# 7_SEGMENT_PCB.net
KiCad netlist of a schematic drawn in EasyEDA
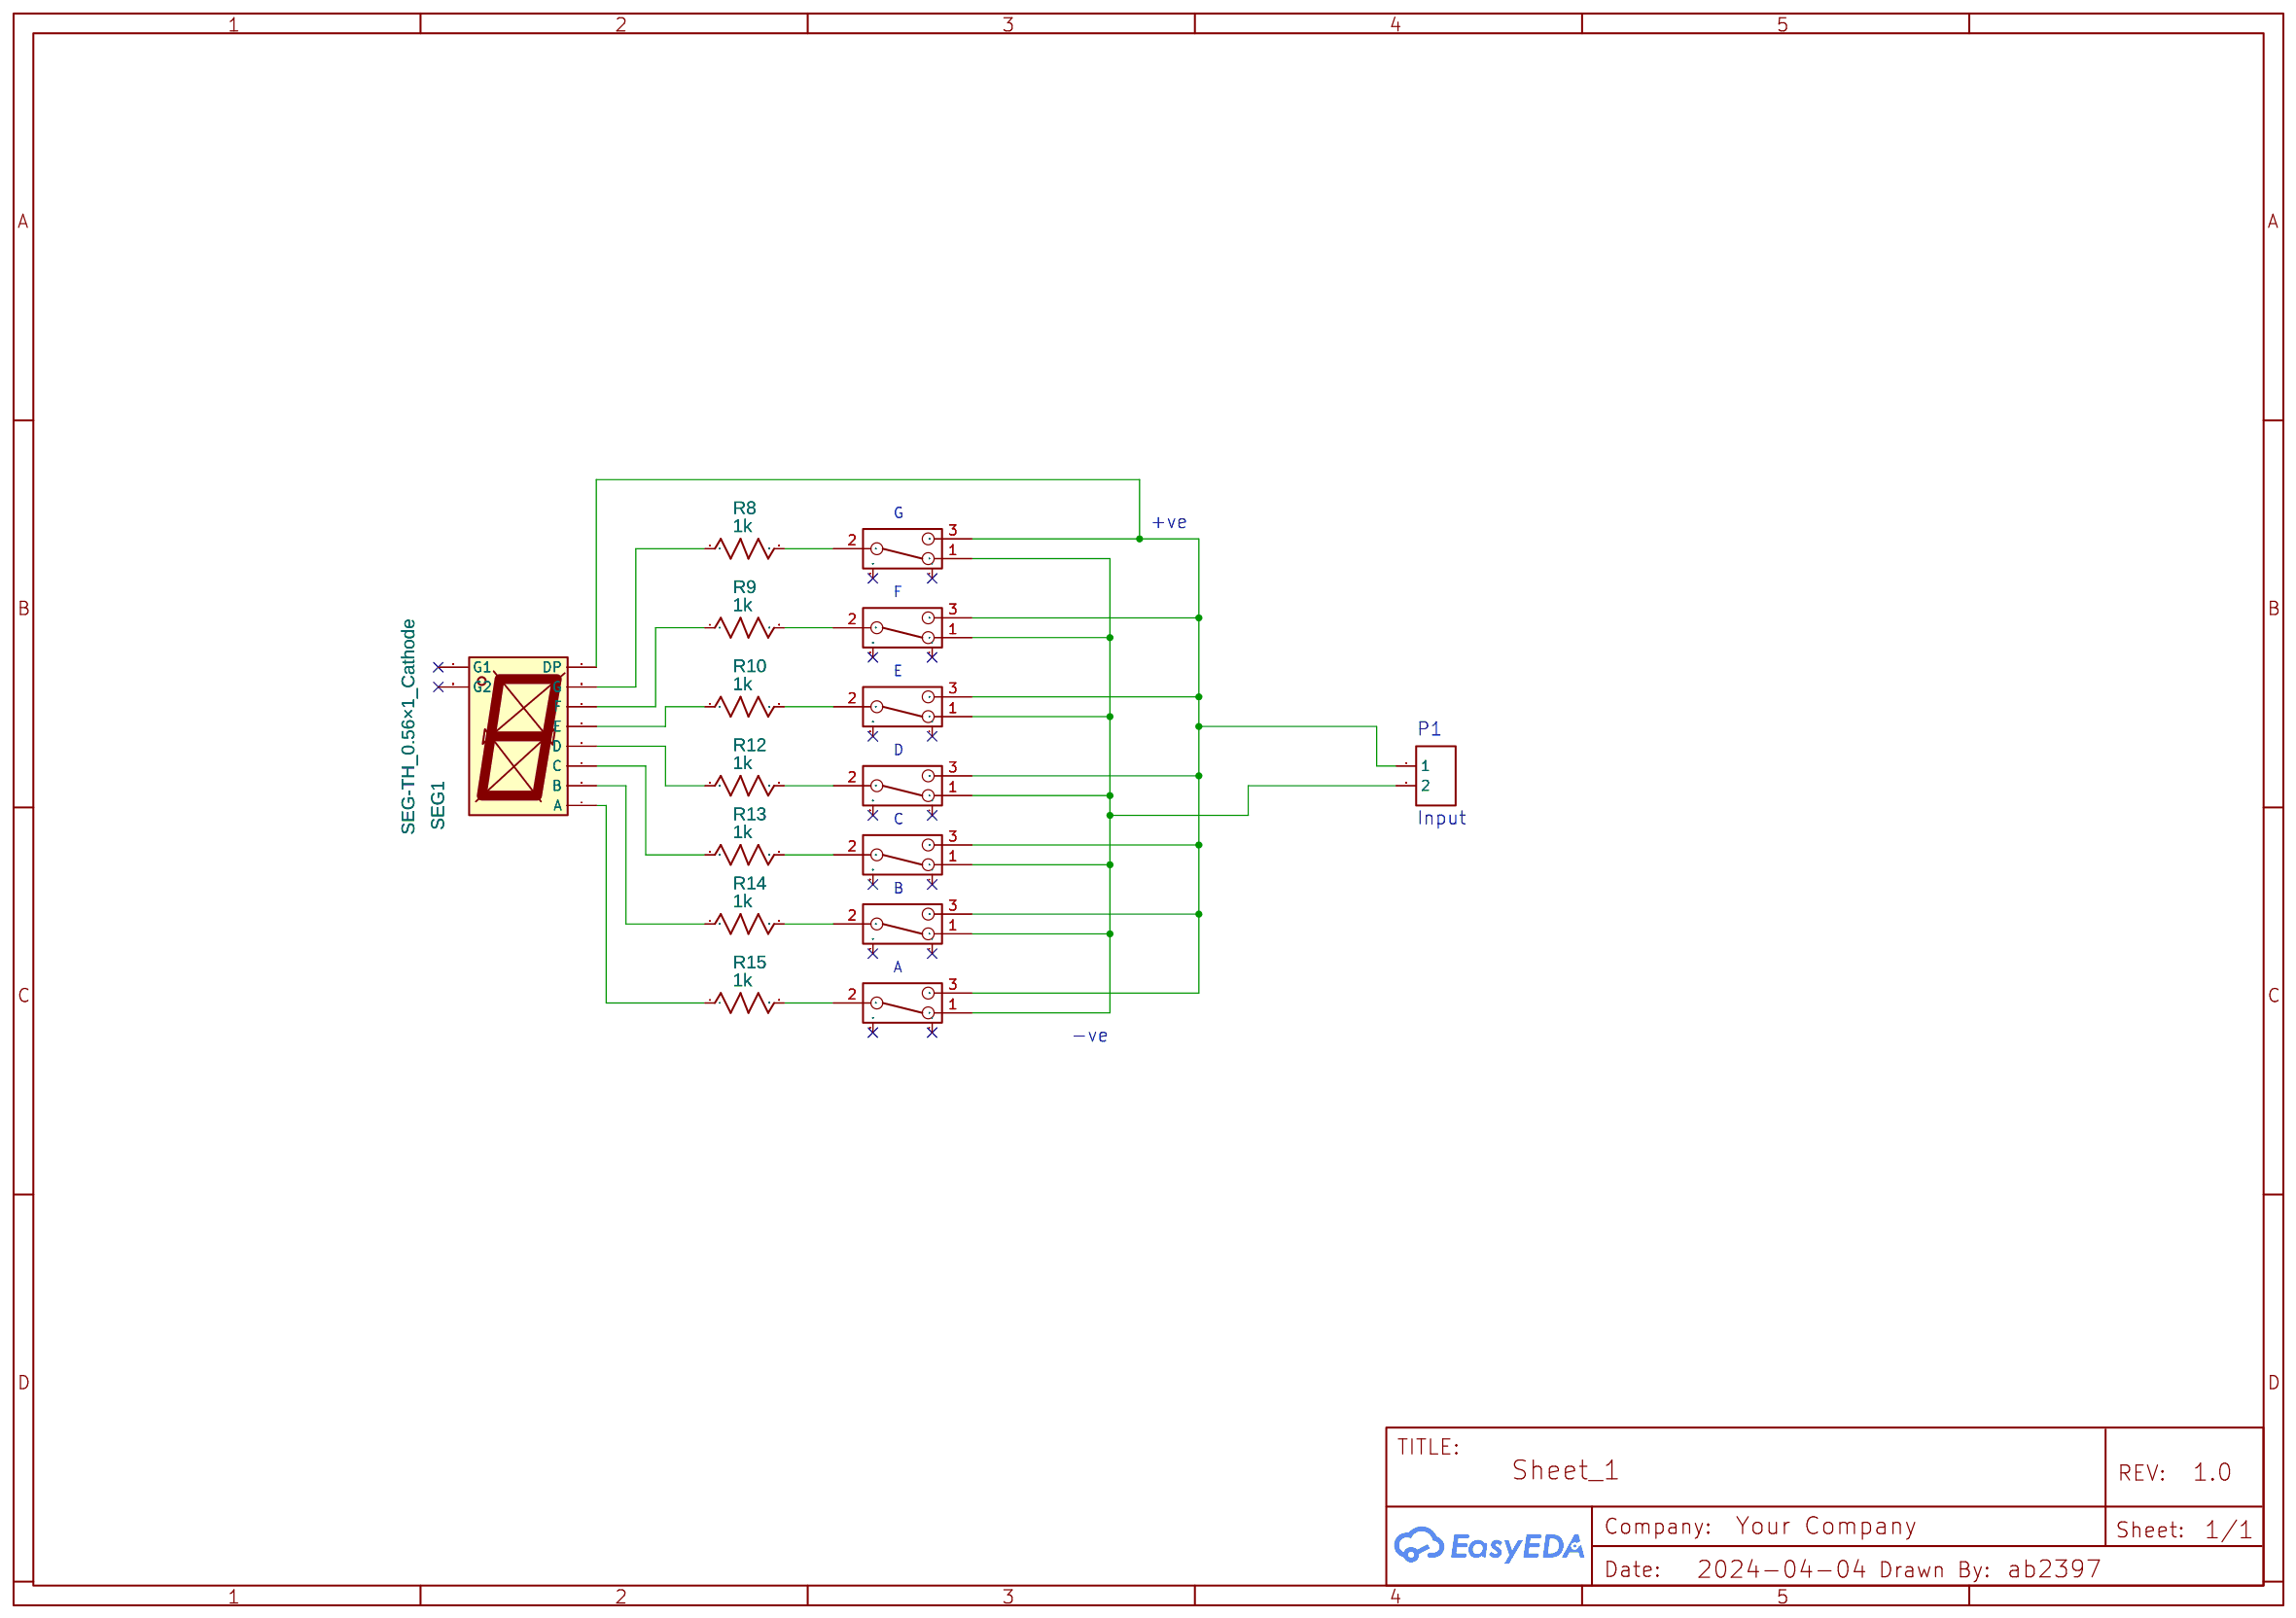
[diagram p0: schematic sheet]

(export (version "E")
  (design (tool "Eeschema 10.0.6"))
  (components
    (comp (ref "H1") (value "HDR-F-2.54_1x2") (libsource (lib "") (part "HDR-F-2.54_1x2")))
    (comp (ref "R8") (value "1k") (libsource (lib "") (part "R_0603_US")))
    (comp (ref "R9") (value "1k") (libsource (lib "") (part "R_0603_US")))
    (comp (ref "R10") (value "1k") (libsource (lib "") (part "R_0603_US")))
    (comp (ref "R12") (value "1k") (libsource (lib "") (part "R_0603_US")))
    (comp (ref "R13") (value "1k") (libsource (lib "") (part "R_0603_US")))
    (comp (ref "R14") (value "1k") (libsource (lib "") (part "R_0603_US")))
    (comp (ref "R15") (value "1k") (libsource (lib "") (part "R_0603_US")))
    (comp (ref "SEG1")
      (value "SEG-TH_0.56×1_Cathode")
      (fields (field (name "Manufacturer") "志浩"))
      (libsource (lib "") (part "SEG-TH_0.56×1_Cathode"))
    )
    (comp (ref "SW1")
      (value "SK-12D02-VG5")
      (fields (field (name "Manufacturer") "Rectangular Connectors - Contacts"))
      (libsource (lib "") (part "SK-12D02-VG5"))
    )
    (comp (ref "SW2")
      (value "SK-12D02-VG5")
      (fields (field (name "Manufacturer") "Rectangular Connectors - Contacts"))
      (libsource (lib "") (part "SK-12D02-VG5"))
    )
    (comp (ref "SW3")
      (value "SK-12D02-VG5")
      (fields (field (name "Manufacturer") "Rectangular Connectors - Contacts"))
      (libsource (lib "") (part "SK-12D02-VG5"))
    )
    (comp (ref "SW4")
      (value "SK-12D02-VG5")
      (fields (field (name "Manufacturer") "Rectangular Connectors - Contacts"))
      (libsource (lib "") (part "SK-12D02-VG5"))
    )
    (comp (ref "SW5")
      (value "SK-12D02-VG5")
      (fields (field (name "Manufacturer") "Rectangular Connectors - Contacts"))
      (libsource (lib "") (part "SK-12D02-VG5"))
    )
    (comp (ref "SW6")
      (value "SK-12D02-VG5")
      (fields (field (name "Manufacturer") "Rectangular Connectors - Contacts"))
      (libsource (lib "") (part "SK-12D02-VG5"))
    )
    (comp (ref "SW7")
      (value "SK-12D02-VG5")
      (fields (field (name "Manufacturer") "Rectangular Connectors - Contacts"))
      (libsource (lib "") (part "SK-12D02-VG5"))
    )
  )
  (nets
    (net (code "1") (name "Net-(H1-Pad2)") (class "Default")
      (node (ref "H1") (pin "2") (pinfunction "2_2") (pintype "input"))
      (node (ref "SW1") (pin "1") (pinfunction "1_1") (pintype "unspecified"))
      (node (ref "SW2") (pin "1") (pinfunction "1_1") (pintype "unspecified"))
      (node (ref "SW3") (pin "1") (pinfunction "1_1") (pintype "unspecified"))
      (node (ref "SW4") (pin "1") (pinfunction "1_1") (pintype "unspecified"))
      (node (ref "SW5") (pin "1") (pinfunction "1_1") (pintype "unspecified"))
      (node (ref "SW6") (pin "1") (pinfunction "1_1") (pintype "unspecified"))
      (node (ref "SW7") (pin "1") (pinfunction "1_1") (pintype "unspecified"))
    )
    (net (code "2") (name "Net-(R8-Pad2)") (class "Default")
      (node (ref "R8") (pin "2") (pinfunction "2_2") (pintype "unspecified"))
      (node (ref "SW1") (pin "2") (pinfunction "2_2") (pintype "unspecified"))
    )
    (net (code "3") (name "Net-(R9-Pad2)") (class "Default")
      (node (ref "R9") (pin "2") (pinfunction "2_2") (pintype "unspecified"))
      (node (ref "SW2") (pin "2") (pinfunction "2_2") (pintype "unspecified"))
    )
    (net (code "4") (name "Net-(R10-Pad2)") (class "Default")
      (node (ref "R10") (pin "2") (pinfunction "2_2") (pintype "unspecified"))
      (node (ref "SW3") (pin "2") (pinfunction "2_2") (pintype "unspecified"))
    )
    (net (code "5") (name "Net-(R12-Pad2)") (class "Default")
      (node (ref "R12") (pin "2") (pinfunction "2_2") (pintype "unspecified"))
      (node (ref "SW4") (pin "2") (pinfunction "2_2") (pintype "unspecified"))
    )
    (net (code "6") (name "Net-(R13-Pad2)") (class "Default")
      (node (ref "R13") (pin "2") (pinfunction "2_2") (pintype "unspecified"))
      (node (ref "SW5") (pin "2") (pinfunction "2_2") (pintype "unspecified"))
    )
    (net (code "7") (name "Net-(R14-Pad2)") (class "Default")
      (node (ref "R14") (pin "2") (pinfunction "2_2") (pintype "unspecified"))
      (node (ref "SW6") (pin "2") (pinfunction "2_2") (pintype "unspecified"))
    )
    (net (code "8") (name "Net-(R15-Pad2)") (class "Default")
      (node (ref "R15") (pin "2") (pinfunction "2_2") (pintype "unspecified"))
      (node (ref "SW7") (pin "2") (pinfunction "2_2") (pintype "unspecified"))
    )
    (net (code "9") (name "Net-(SEG1-A)") (class "Default")
      (node (ref "R15") (pin "1") (pinfunction "1_1") (pintype "unspecified"))
      (node (ref "SEG1") (pin "7") (pinfunction "A_7") (pintype "unspecified"))
    )
    (net (code "10") (name "Net-(SEG1-B)") (class "Default")
      (node (ref "R14") (pin "1") (pinfunction "1_1") (pintype "unspecified"))
      (node (ref "SEG1") (pin "6") (pinfunction "B_6") (pintype "unspecified"))
    )
    (net (code "11") (name "Net-(SEG1-C)") (class "Default")
      (node (ref "R13") (pin "1") (pinfunction "1_1") (pintype "unspecified"))
      (node (ref "SEG1") (pin "4") (pinfunction "C_4") (pintype "unspecified"))
    )
    (net (code "12") (name "Net-(SEG1-D)") (class "Default")
      (node (ref "R12") (pin "1") (pinfunction "1_1") (pintype "unspecified"))
      (node (ref "SEG1") (pin "2") (pinfunction "D_2") (pintype "unspecified"))
    )
    (net (code "13") (name "Net-(SEG1-DP)") (class "Default")
      (node (ref "H1") (pin "1") (pinfunction "1_1") (pintype "input"))
      (node (ref "SEG1") (pin "5") (pinfunction "DP_5") (pintype "unspecified"))
      (node (ref "SW1") (pin "3") (pinfunction "3_3") (pintype "unspecified"))
      (node (ref "SW2") (pin "3") (pinfunction "3_3") (pintype "unspecified"))
      (node (ref "SW3") (pin "3") (pinfunction "3_3") (pintype "unspecified"))
      (node (ref "SW4") (pin "3") (pinfunction "3_3") (pintype "unspecified"))
      (node (ref "SW5") (pin "3") (pinfunction "3_3") (pintype "unspecified"))
      (node (ref "SW6") (pin "3") (pinfunction "3_3") (pintype "unspecified"))
      (node (ref "SW7") (pin "3") (pinfunction "3_3") (pintype "unspecified"))
    )
    (net (code "14") (name "Net-(SEG1-E)") (class "Default")
      (node (ref "R10") (pin "1") (pinfunction "1_1") (pintype "unspecified"))
      (node (ref "SEG1") (pin "1") (pinfunction "E_1") (pintype "unspecified"))
    )
    (net (code "15") (name "Net-(SEG1-F)") (class "Default")
      (node (ref "R9") (pin "1") (pinfunction "1_1") (pintype "unspecified"))
      (node (ref "SEG1") (pin "9") (pinfunction "F_9") (pintype "unspecified"))
    )
    (net (code "16") (name "Net-(SEG1-G)") (class "Default")
      (node (ref "R8") (pin "1") (pinfunction "1_1") (pintype "unspecified"))
      (node (ref "SEG1") (pin "10") (pinfunction "G_10") (pintype "unspecified"))
    )
    (net (code "17") (name "unconnected-(SEG1-G1-Pad3)") (class "Default")
      (node (ref "SEG1") (pin "3") (pinfunction "G1_3") (pintype "unspecified+no_connect"))
    )
    (net (code "18") (name "unconnected-(SEG1-G2-Pad8)") (class "Default")
      (node (ref "SEG1") (pin "8") (pinfunction "G2_8") (pintype "unspecified+no_connect"))
    )
    (net (code "19") (name "unconnected-(SW1-Pad4)") (class "Default")
      (node (ref "SW1") (pin "4") (pinfunction "4_4") (pintype "unspecified+no_connect"))
    )
    (net (code "20") (name "unconnected-(SW1-Pad5)") (class "Default")
      (node (ref "SW1") (pin "5") (pinfunction "5_5") (pintype "unspecified+no_connect"))
    )
    (net (code "21") (name "unconnected-(SW2-Pad4)") (class "Default")
      (node (ref "SW2") (pin "4") (pinfunction "4_4") (pintype "unspecified+no_connect"))
    )
    (net (code "22") (name "unconnected-(SW2-Pad5)") (class "Default")
      (node (ref "SW2") (pin "5") (pinfunction "5_5") (pintype "unspecified+no_connect"))
    )
    (net (code "23") (name "unconnected-(SW3-Pad4)") (class "Default")
      (node (ref "SW3") (pin "4") (pinfunction "4_4") (pintype "unspecified+no_connect"))
    )
    (net (code "24") (name "unconnected-(SW3-Pad5)") (class "Default")
      (node (ref "SW3") (pin "5") (pinfunction "5_5") (pintype "unspecified+no_connect"))
    )
    (net (code "25") (name "unconnected-(SW4-Pad4)") (class "Default")
      (node (ref "SW4") (pin "4") (pinfunction "4_4") (pintype "unspecified+no_connect"))
    )
    (net (code "26") (name "unconnected-(SW4-Pad5)") (class "Default")
      (node (ref "SW4") (pin "5") (pinfunction "5_5") (pintype "unspecified+no_connect"))
    )
    (net (code "27") (name "unconnected-(SW5-Pad4)") (class "Default")
      (node (ref "SW5") (pin "4") (pinfunction "4_4") (pintype "unspecified+no_connect"))
    )
    (net (code "28") (name "unconnected-(SW5-Pad5)") (class "Default")
      (node (ref "SW5") (pin "5") (pinfunction "5_5") (pintype "unspecified+no_connect"))
    )
    (net (code "29") (name "unconnected-(SW6-Pad4)") (class "Default")
      (node (ref "SW6") (pin "4") (pinfunction "4_4") (pintype "unspecified+no_connect"))
    )
    (net (code "30") (name "unconnected-(SW6-Pad5)") (class "Default")
      (node (ref "SW6") (pin "5") (pinfunction "5_5") (pintype "unspecified+no_connect"))
    )
    (net (code "31") (name "unconnected-(SW7-Pad4)") (class "Default")
      (node (ref "SW7") (pin "4") (pinfunction "4_4") (pintype "unspecified+no_connect"))
    )
    (net (code "32") (name "unconnected-(SW7-Pad5)") (class "Default")
      (node (ref "SW7") (pin "5") (pinfunction "5_5") (pintype "unspecified+no_connect"))
    )
  )
)
